# inclinometro.net
KiCad netlist of a schematic drawn in EAGLE
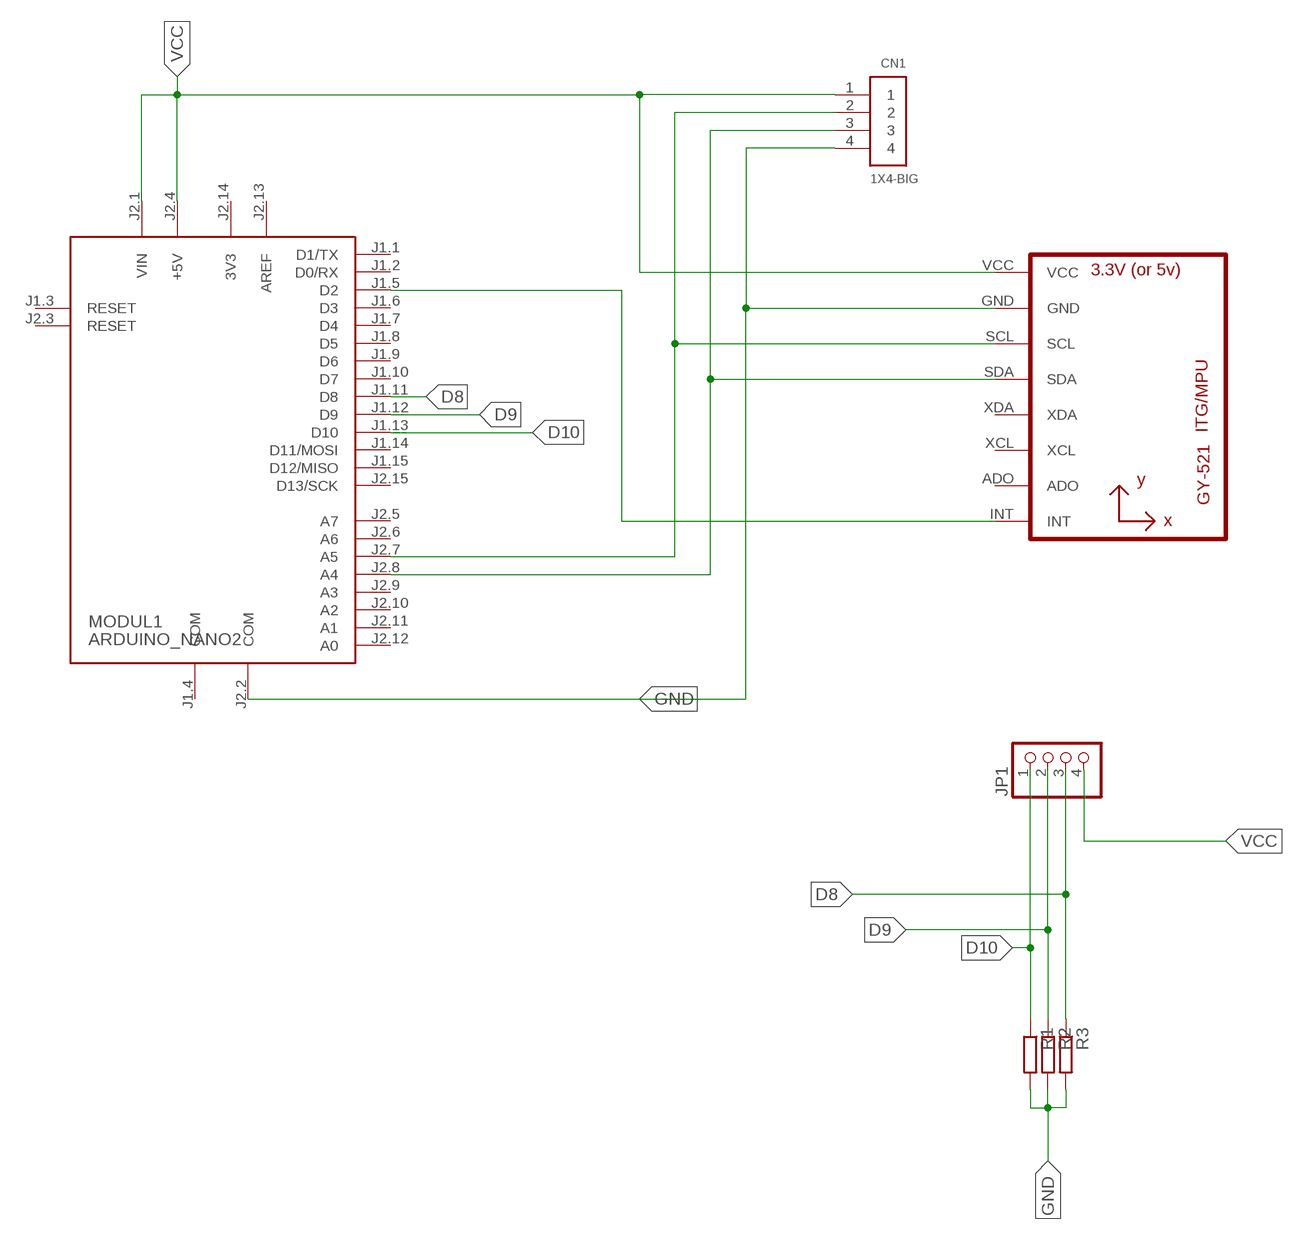
[diagram p0: schematic, sheet 1]

(export (version "E")
  (design (tool "Eeschema 10.0.6"))
  (components
    (comp (ref "CN1")
      (value "1X4-BIG")
      (footprint "eagle-import:1X04-BIG")
      (libsource (lib "eagle-import") (part "1X4-BIG"))
    )
    (comp (ref "JP1")
      (value "PINHD-1X4")
      (footprint "eagle-import:1X04")
      (libsource (lib "eagle-import") (part "PINHD-1X4"))
    )
    (comp (ref "MODUL1")
      (value "ARDUINO_NANO2")
      (footprint "eagle-import:ARDUINO_NANO2")
      (libsource (lib "eagle-import") (part "ARDUINO_NANO2"))
    )
    (comp (ref "R1")
      (value "R-EU_0207/10")
      (footprint "eagle-import:0207_10")
      (libsource (lib "eagle-import") (part "R-EU_0207/10"))
    )
    (comp (ref "R2")
      (value "R-EU_0207/10")
      (footprint "eagle-import:0207_10")
      (libsource (lib "eagle-import") (part "R-EU_0207/10"))
    )
    (comp (ref "R3")
      (value "R-EU_0207/10")
      (footprint "eagle-import:0207_10")
      (libsource (lib "eagle-import") (part "R-EU_0207/10"))
    )
    (comp (ref "U1")
      (value "GY-521MPU6050")
      (footprint "eagle-import:GY-521")
      (libsource (lib "eagle-import") (part "GY-521MPU6050"))
    )
  )
  (nets
    (net (code "1") (name "/3V3") (class "Default")
      (node (ref "MODUL1") (pin "J2.14") (pinfunction "3V3_J2.14") (pintype "power_in"))
    )
    (net (code "2") (name "/AREF") (class "Default")
      (node (ref "MODUL1") (pin "J2.13") (pinfunction "AREF_J2.13") (pintype "power_in"))
    )
    (net (code "3") (name "/COM") (class "Default")
      (node (ref "MODUL1") (pin "J1.4") (pinfunction "COM_J1.4") (pintype "power_in"))
    )
    (net (code "4") (name "D8") (class "Default")
      (node (ref "JP1") (pin "3") (pinfunction "3_3") (pintype "passive"))
      (node (ref "MODUL1") (pin "J1.11") (pinfunction "D8_J1.11") (pintype "bidirectional"))
      (node (ref "R3") (pin "1") (pinfunction "1_1") (pintype "passive"))
    )
    (net (code "5") (name "D9") (class "Default")
      (node (ref "JP1") (pin "2") (pinfunction "2_2") (pintype "passive"))
      (node (ref "MODUL1") (pin "J1.12") (pinfunction "D9_J1.12") (pintype "bidirectional"))
      (node (ref "R2") (pin "1") (pinfunction "1_1") (pintype "passive"))
    )
    (net (code "6") (name "D10") (class "Default")
      (node (ref "JP1") (pin "1") (pinfunction "1_1") (pintype "passive"))
      (node (ref "MODUL1") (pin "J1.13") (pinfunction "D10_J1.13") (pintype "bidirectional"))
      (node (ref "R1") (pin "1") (pinfunction "1_1") (pintype "passive"))
    )
    (net (code "7") (name "GND") (class "Default")
      (node (ref "CN1") (pin "4") (pinfunction "4_4") (pintype "bidirectional"))
      (node (ref "MODUL1") (pin "J2.2") (pinfunction "COM_J2.2") (pintype "power_in"))
      (node (ref "R1") (pin "2") (pinfunction "2_2") (pintype "passive"))
      (node (ref "R2") (pin "2") (pinfunction "2_2") (pintype "passive"))
      (node (ref "R3") (pin "2") (pinfunction "2_2") (pintype "passive"))
      (node (ref "U1") (pin "GND") (pinfunction "GND_GND") (pintype "bidirectional"))
    )
    (net (code "8") (name "Net-(MODUL1-A4)") (class "Default")
      (node (ref "CN1") (pin "3") (pinfunction "3_3") (pintype "bidirectional"))
      (node (ref "MODUL1") (pin "J2.8") (pinfunction "A4_J2.8") (pintype "bidirectional"))
      (node (ref "U1") (pin "SDA") (pinfunction "SDA_SDA") (pintype "bidirectional"))
    )
    (net (code "9") (name "Net-(MODUL1-A5)") (class "Default")
      (node (ref "CN1") (pin "2") (pinfunction "2_2") (pintype "bidirectional"))
      (node (ref "MODUL1") (pin "J2.7") (pinfunction "A5_J2.7") (pintype "bidirectional"))
      (node (ref "U1") (pin "SCL") (pinfunction "SCL_SCL") (pintype "bidirectional"))
    )
    (net (code "10") (name "Net-(MODUL1-D2)") (class "Default")
      (node (ref "MODUL1") (pin "J1.5") (pinfunction "D2_J1.5") (pintype "bidirectional"))
      (node (ref "U1") (pin "INT") (pinfunction "INT_INT") (pintype "bidirectional"))
    )
    (net (code "11") (name "VCC") (class "Default")
      (node (ref "CN1") (pin "1") (pinfunction "1_1") (pintype "bidirectional"))
      (node (ref "JP1") (pin "4") (pinfunction "4_4") (pintype "passive"))
      (node (ref "MODUL1") (pin "J2.1") (pinfunction "VIN_J2.1") (pintype "power_in"))
      (node (ref "MODUL1") (pin "J2.4") (pinfunction "+5V_J2.4") (pintype "power_in"))
      (node (ref "U1") (pin "VCC") (pinfunction "VCC_VCC") (pintype "bidirectional"))
    )
    (net (code "12") (name "unconnected-(MODUL1-A0-PadJ2.12)") (class "Default")
      (node (ref "MODUL1") (pin "J2.12") (pinfunction "A0_J2.12") (pintype "bidirectional"))
    )
    (net (code "13") (name "unconnected-(MODUL1-A1-PadJ2.11)") (class "Default")
      (node (ref "MODUL1") (pin "J2.11") (pinfunction "A1_J2.11") (pintype "bidirectional"))
    )
    (net (code "14") (name "unconnected-(MODUL1-A2-PadJ2.10)") (class "Default")
      (node (ref "MODUL1") (pin "J2.10") (pinfunction "A2_J2.10") (pintype "bidirectional"))
    )
    (net (code "15") (name "unconnected-(MODUL1-A3-PadJ2.9)") (class "Default")
      (node (ref "MODUL1") (pin "J2.9") (pinfunction "A3_J2.9") (pintype "bidirectional"))
    )
    (net (code "16") (name "unconnected-(MODUL1-A6-PadJ2.6)") (class "Default")
      (node (ref "MODUL1") (pin "J2.6") (pinfunction "A6_J2.6") (pintype "bidirectional"))
    )
    (net (code "17") (name "unconnected-(MODUL1-A7-PadJ2.5)") (class "Default")
      (node (ref "MODUL1") (pin "J2.5") (pinfunction "A7_J2.5") (pintype "bidirectional"))
    )
    (net (code "18") (name "unconnected-(MODUL1-D0{slash}RX-PadJ1.2)") (class "Default")
      (node (ref "MODUL1") (pin "J1.2") (pinfunction "D0/RX_J1.2") (pintype "bidirectional"))
    )
    (net (code "19") (name "unconnected-(MODUL1-D1{slash}TX-PadJ1.1)") (class "Default")
      (node (ref "MODUL1") (pin "J1.1") (pinfunction "D1/TX_J1.1") (pintype "bidirectional"))
    )
    (net (code "20") (name "unconnected-(MODUL1-D3-PadJ1.6)") (class "Default")
      (node (ref "MODUL1") (pin "J1.6") (pinfunction "D3_J1.6") (pintype "bidirectional"))
    )
    (net (code "21") (name "unconnected-(MODUL1-D4-PadJ1.7)") (class "Default")
      (node (ref "MODUL1") (pin "J1.7") (pinfunction "D4_J1.7") (pintype "bidirectional"))
    )
    (net (code "22") (name "unconnected-(MODUL1-D5-PadJ1.8)") (class "Default")
      (node (ref "MODUL1") (pin "J1.8") (pinfunction "D5_J1.8") (pintype "bidirectional"))
    )
    (net (code "23") (name "unconnected-(MODUL1-D6-PadJ1.9)") (class "Default")
      (node (ref "MODUL1") (pin "J1.9") (pinfunction "D6_J1.9") (pintype "bidirectional"))
    )
    (net (code "24") (name "unconnected-(MODUL1-D7-PadJ1.10)") (class "Default")
      (node (ref "MODUL1") (pin "J1.10") (pinfunction "D7_J1.10") (pintype "bidirectional"))
    )
    (net (code "25") (name "unconnected-(MODUL1-D11{slash}MOSI-PadJ1.14)") (class "Default")
      (node (ref "MODUL1") (pin "J1.14") (pinfunction "D11/MOSI_J1.14") (pintype "bidirectional"))
    )
    (net (code "26") (name "unconnected-(MODUL1-D12{slash}MISO-PadJ1.15)") (class "Default")
      (node (ref "MODUL1") (pin "J1.15") (pinfunction "D12/MISO_J1.15") (pintype "bidirectional"))
    )
    (net (code "27") (name "unconnected-(MODUL1-D13{slash}SCK-PadJ2.15)") (class "Default")
      (node (ref "MODUL1") (pin "J2.15") (pinfunction "D13/SCK_J2.15") (pintype "bidirectional"))
    )
    (net (code "28") (name "unconnected-(MODUL1-RESET-PadJ1.3)") (class "Default")
      (node (ref "MODUL1") (pin "J1.3") (pinfunction "RESET_J1.3") (pintype "bidirectional"))
    )
    (net (code "29") (name "unconnected-(MODUL1-RESET-PadJ2.3)") (class "Default")
      (node (ref "MODUL1") (pin "J2.3") (pinfunction "RESET_J2.3") (pintype "bidirectional"))
    )
    (net (code "30") (name "unconnected-(U1-PadADO)") (class "Default")
      (node (ref "U1") (pin "ADO") (pinfunction "ADO_ADO") (pintype "bidirectional"))
    )
    (net (code "31") (name "unconnected-(U1-PadXCL)") (class "Default")
      (node (ref "U1") (pin "XCL") (pinfunction "XCL_XCL") (pintype "bidirectional"))
    )
    (net (code "32") (name "unconnected-(U1-PadXDA)") (class "Default")
      (node (ref "U1") (pin "XDA") (pinfunction "XDA_XDA") (pintype "bidirectional"))
    )
  )
)
